# mixer.net
KiCad netlist of a schematic drawn in Altium Designer
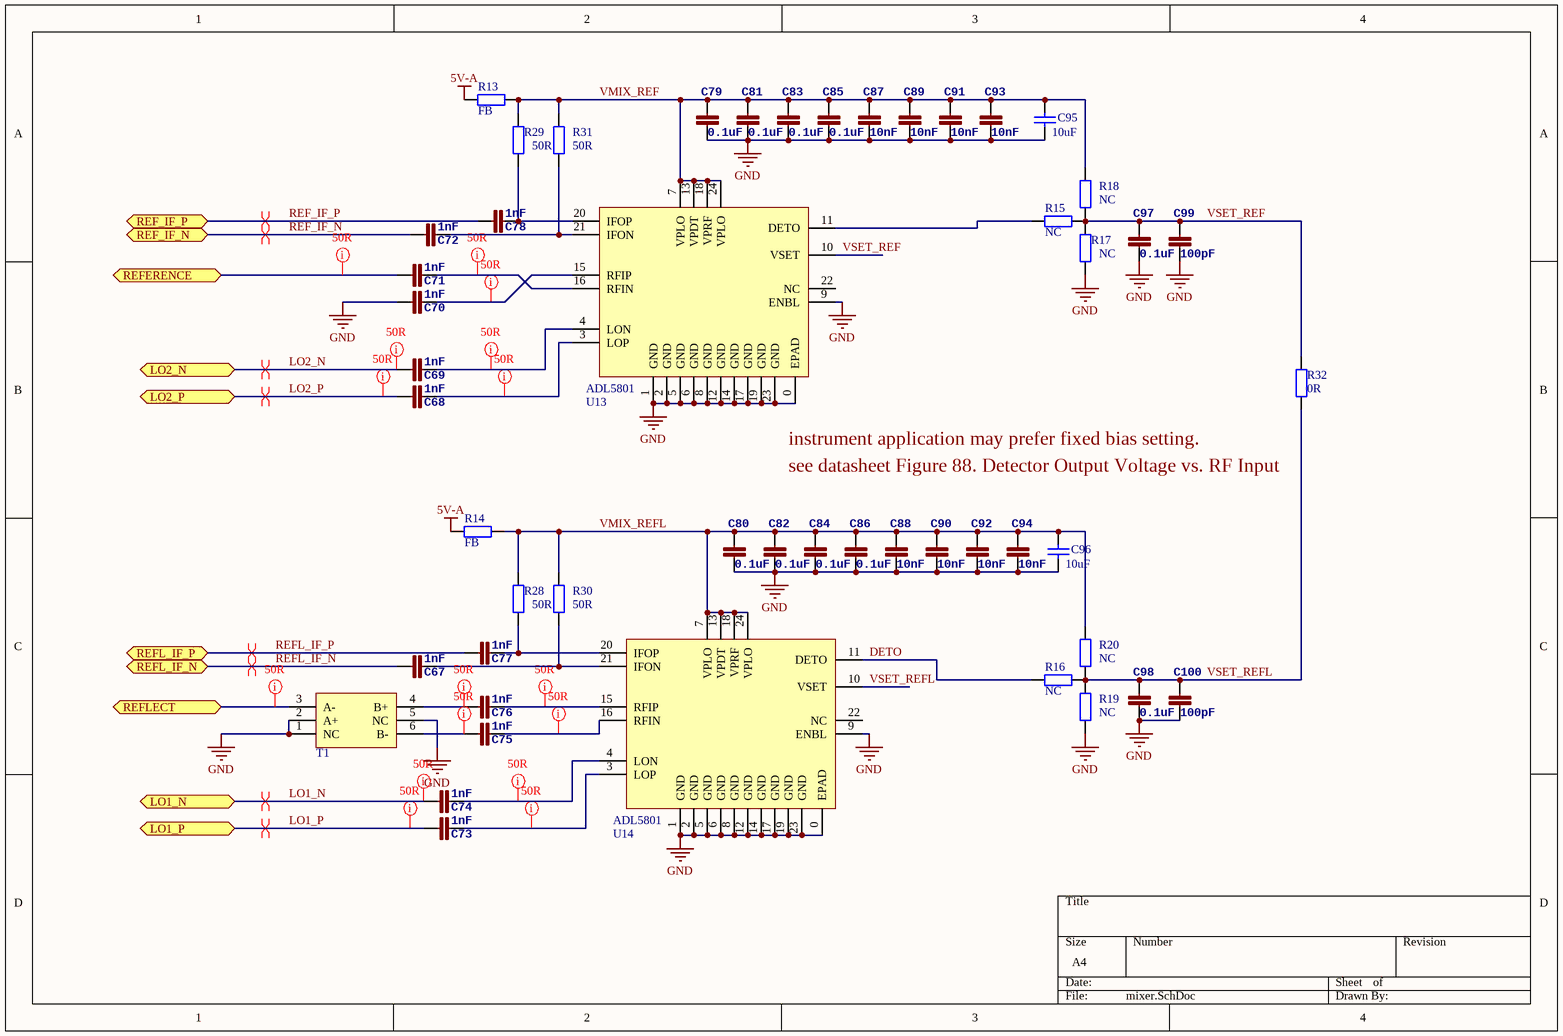
[diagram p0: mixer.SchDoc]

(export (version "E")
  (design (tool "Eeschema 10.0.6"))
  (components
    (comp (ref "C67")
      (value "1nF")
      (footprint "0402")
      (description "<b>Capacitor</b>\nStandard 0603 ceramic capacitor, and 0.1\" leaded capacitor.")
      (fields (field (name "PARTNO") "CC0402ZRY5V7BB104"))
      (libsource (lib "*") (part "CAP0402-CAP"))
    )
    (comp (ref "C68")
      (value "1nF")
      (footprint "0402")
      (description "<b>Capacitor</b>\nStandard 0603 ceramic capacitor, and 0.1\" leaded capacitor.")
      (fields (field (name "PARTNO") "CC0402ZRY5V7BB104"))
      (libsource (lib "*") (part "CAP0402-CAP"))
    )
    (comp (ref "C69")
      (value "1nF")
      (footprint "0402")
      (description "<b>Capacitor</b>\nStandard 0603 ceramic capacitor, and 0.1\" leaded capacitor.")
      (fields (field (name "PARTNO") "CC0402ZRY5V7BB104"))
      (libsource (lib "*") (part "CAP0402-CAP"))
    )
    (comp (ref "C70")
      (value "1nF")
      (footprint "0402")
      (description "<b>Capacitor</b>\nStandard 0603 ceramic capacitor, and 0.1\" leaded capacitor.")
      (fields (field (name "PARTNO") "CC0402ZRY5V7BB104"))
      (libsource (lib "*") (part "CAP0402-CAP"))
    )
    (comp (ref "C71")
      (value "1nF")
      (footprint "0402")
      (description "<b>Capacitor</b>\nStandard 0603 ceramic capacitor, and 0.1\" leaded capacitor.")
      (fields (field (name "PARTNO") "CC0402ZRY5V7BB104"))
      (libsource (lib "*") (part "CAP0402-CAP"))
    )
    (comp (ref "C72")
      (value "1nF")
      (footprint "0402")
      (description "<b>Capacitor</b>\nStandard 0603 ceramic capacitor, and 0.1\" leaded capacitor.")
      (fields (field (name "PARTNO") "CC0402ZRY5V7BB104"))
      (libsource (lib "*") (part "CAP0402-CAP"))
    )
    (comp (ref "C73")
      (value "1nF")
      (footprint "0402")
      (description "<b>Capacitor</b>\nStandard 0603 ceramic capacitor, and 0.1\" leaded capacitor.")
      (fields (field (name "PARTNO") "CC0402ZRY5V7BB104"))
      (libsource (lib "*") (part "CAP0402-CAP"))
    )
    (comp (ref "C74")
      (value "1nF")
      (footprint "0402")
      (description "<b>Capacitor</b>\nStandard 0603 ceramic capacitor, and 0.1\" leaded capacitor.")
      (fields (field (name "PARTNO") "CC0402ZRY5V7BB104"))
      (libsource (lib "*") (part "CAP0402-CAP"))
    )
    (comp (ref "C75")
      (value "1nF")
      (footprint "0402")
      (description "<b>Capacitor</b>\nStandard 0603 ceramic capacitor, and 0.1\" leaded capacitor.")
      (fields (field (name "PARTNO") "CC0402ZRY5V7BB104"))
      (libsource (lib "*") (part "CAP0402-CAP"))
    )
    (comp (ref "C76")
      (value "1nF")
      (footprint "0402")
      (description "<b>Capacitor</b>\nStandard 0603 ceramic capacitor, and 0.1\" leaded capacitor.")
      (fields (field (name "PARTNO") "CC0402ZRY5V7BB104"))
      (libsource (lib "*") (part "CAP0402-CAP"))
    )
    (comp (ref "C77")
      (value "1nF")
      (footprint "0402")
      (description "<b>Capacitor</b>\nStandard 0603 ceramic capacitor, and 0.1\" leaded capacitor.")
      (fields (field (name "PARTNO") "CC0402ZRY5V7BB104"))
      (libsource (lib "*") (part "CAP0402-CAP"))
    )
    (comp (ref "C78")
      (value "1nF")
      (footprint "0402")
      (description "<b>Capacitor</b>\nStandard 0603 ceramic capacitor, and 0.1\" leaded capacitor.")
      (fields (field (name "PARTNO") "CC0402ZRY5V7BB104"))
      (libsource (lib "*") (part "CAP0402-CAP"))
    )
    (comp (ref "C79")
      (value "0.1uF")
      (footprint "0402")
      (description "<b>Capacitor</b>\nStandard 0603 ceramic capacitor, and 0.1\" leaded capacitor.")
      (fields (field (name "PARTNO") "CC0402ZRY5V7BB104"))
      (libsource (lib "") (part "CAP0402-CAP_1"))
    )
    (comp (ref "C80")
      (value "0.1uF")
      (footprint "0402")
      (description "<b>Capacitor</b>\nStandard 0603 ceramic capacitor, and 0.1\" leaded capacitor.")
      (fields (field (name "PARTNO") "CC0402ZRY5V7BB104"))
      (libsource (lib "") (part "CAP0402-CAP_1"))
    )
    (comp (ref "C81")
      (value "0.1uF")
      (footprint "0402")
      (description "<b>Capacitor</b>\nStandard 0603 ceramic capacitor, and 0.1\" leaded capacitor.")
      (fields (field (name "PARTNO") "CC0402ZRY5V7BB104"))
      (libsource (lib "") (part "CAP0402-CAP_1"))
    )
    (comp (ref "C82")
      (value "0.1uF")
      (footprint "0402")
      (description "<b>Capacitor</b>\nStandard 0603 ceramic capacitor, and 0.1\" leaded capacitor.")
      (fields (field (name "PARTNO") "CC0402ZRY5V7BB104"))
      (libsource (lib "") (part "CAP0402-CAP_1"))
    )
    (comp (ref "C83")
      (value "0.1uF")
      (footprint "0402")
      (description "<b>Capacitor</b>\nStandard 0603 ceramic capacitor, and 0.1\" leaded capacitor.")
      (fields (field (name "PARTNO") "CC0402ZRY5V7BB104"))
      (libsource (lib "") (part "CAP0402-CAP_1"))
    )
    (comp (ref "C84")
      (value "0.1uF")
      (footprint "0402")
      (description "<b>Capacitor</b>\nStandard 0603 ceramic capacitor, and 0.1\" leaded capacitor.")
      (fields (field (name "PARTNO") "CC0402ZRY5V7BB104"))
      (libsource (lib "") (part "CAP0402-CAP_1"))
    )
    (comp (ref "C85")
      (value "0.1uF")
      (footprint "0402")
      (description "<b>Capacitor</b>\nStandard 0603 ceramic capacitor, and 0.1\" leaded capacitor.")
      (fields (field (name "PARTNO") "CC0402ZRY5V7BB104"))
      (libsource (lib "") (part "CAP0402-CAP_1"))
    )
    (comp (ref "C86")
      (value "0.1uF")
      (footprint "0402")
      (description "<b>Capacitor</b>\nStandard 0603 ceramic capacitor, and 0.1\" leaded capacitor.")
      (fields (field (name "PARTNO") "CC0402ZRY5V7BB104"))
      (libsource (lib "") (part "CAP0402-CAP_1"))
    )
    (comp (ref "C87")
      (value "10nF")
      (footprint "0402")
      (description "<b>Capacitor</b>\nStandard 0603 ceramic capacitor, and 0.1\" leaded capacitor.")
      (fields (field (name "PARTNO") "CC0402ZRY5V7BB104"))
      (libsource (lib "") (part "CAP0402-CAP_1"))
    )
    (comp (ref "C88")
      (value "10nF")
      (footprint "0402")
      (description "<b>Capacitor</b>\nStandard 0603 ceramic capacitor, and 0.1\" leaded capacitor.")
      (fields (field (name "PARTNO") "CC0402ZRY5V7BB104"))
      (libsource (lib "") (part "CAP0402-CAP_1"))
    )
    (comp (ref "C89")
      (value "10nF")
      (footprint "0402")
      (description "<b>Capacitor</b>\nStandard 0603 ceramic capacitor, and 0.1\" leaded capacitor.")
      (fields (field (name "PARTNO") "CC0402ZRY5V7BB104"))
      (libsource (lib "") (part "CAP0402-CAP_1"))
    )
    (comp (ref "C90")
      (value "10nF")
      (footprint "0402")
      (description "<b>Capacitor</b>\nStandard 0603 ceramic capacitor, and 0.1\" leaded capacitor.")
      (fields (field (name "PARTNO") "CC0402ZRY5V7BB104"))
      (libsource (lib "") (part "CAP0402-CAP_1"))
    )
    (comp (ref "C91")
      (value "10nF")
      (footprint "0402")
      (description "<b>Capacitor</b>\nStandard 0603 ceramic capacitor, and 0.1\" leaded capacitor.")
      (fields (field (name "PARTNO") "CC0402ZRY5V7BB104"))
      (libsource (lib "") (part "CAP0402-CAP_1"))
    )
    (comp (ref "C92")
      (value "10nF")
      (footprint "0402")
      (description "<b>Capacitor</b>\nStandard 0603 ceramic capacitor, and 0.1\" leaded capacitor.")
      (fields (field (name "PARTNO") "CC0402ZRY5V7BB104"))
      (libsource (lib "") (part "CAP0402-CAP_1"))
    )
    (comp (ref "C93")
      (value "10nF")
      (footprint "0402")
      (description "<b>Capacitor</b>\nStandard 0603 ceramic capacitor, and 0.1\" leaded capacitor.")
      (fields (field (name "PARTNO") "CC0402ZRY5V7BB104"))
      (libsource (lib "") (part "CAP0402-CAP_1"))
    )
    (comp (ref "C94")
      (value "10nF")
      (footprint "0402")
      (description "<b>Capacitor</b>\nStandard 0603 ceramic capacitor, and 0.1\" leaded capacitor.")
      (fields (field (name "PARTNO") "CC0402ZRY5V7BB104"))
      (libsource (lib "") (part "CAP0402-CAP_1"))
    )
    (comp (ref "C95")
      (value "10uF")
      (footprint "0805")
      (description "Capacitor")
      (fields (field (name "PUBLISHER") "Altium Limited"))
      (libsource (lib "RTC6705") (part "Cap"))
    )
    (comp (ref "C96")
      (value "10uF")
      (footprint "0805")
      (description "Capacitor")
      (fields (field (name "PUBLISHER") "Altium Limited"))
      (libsource (lib "RTC6705") (part "Cap"))
    )
    (comp (ref "C97")
      (value "0.1uF")
      (footprint "0402")
      (description "<b>Capacitor</b>\nStandard 0603 ceramic capacitor, and 0.1\" leaded capacitor.")
      (fields (field (name "PARTNO") "CC0402ZRY5V7BB104"))
      (libsource (lib "") (part "CAP0402-CAP_1"))
    )
    (comp (ref "C98")
      (value "0.1uF")
      (footprint "0402")
      (description "<b>Capacitor</b>\nStandard 0603 ceramic capacitor, and 0.1\" leaded capacitor.")
      (fields (field (name "PARTNO") "CC0402ZRY5V7BB104"))
      (libsource (lib "") (part "CAP0402-CAP_1"))
    )
    (comp (ref "C99")
      (value "100pF")
      (footprint "0402")
      (description "<b>Capacitor</b>\nStandard 0603 ceramic capacitor, and 0.1\" leaded capacitor.")
      (fields (field (name "PARTNO") "CC0402ZRY5V7BB104"))
      (libsource (lib "") (part "CAP0402-CAP_1"))
    )
    (comp (ref "C100")
      (value "100pF")
      (footprint "0402")
      (description "<b>Capacitor</b>\nStandard 0603 ceramic capacitor, and 0.1\" leaded capacitor.")
      (fields (field (name "PARTNO") "CC0402ZRY5V7BB104"))
      (libsource (lib "") (part "CAP0402-CAP_1"))
    )
    (comp (ref "R13")
      (value "FB")
      (footprint "0603")
      (description "Resistor")
      (fields (field (name "PUBLISHER") "Altium Limited"))
      (libsource (lib "Miscellaneous Devices") (part "Res2"))
    )
    (comp (ref "R14")
      (value "FB")
      (footprint "0603")
      (description "Resistor")
      (fields (field (name "PUBLISHER") "Altium Limited"))
      (libsource (lib "Miscellaneous Devices") (part "Res2"))
    )
    (comp (ref "R15")
      (value "NC")
      (footprint "0402")
      (description "Resistor")
      (fields (field (name "PUBLISHER") "Altium Limited"))
      (libsource (lib "") (part "Res2_2"))
    )
    (comp (ref "R16")
      (value "NC")
      (footprint "0402")
      (description "Resistor")
      (fields (field (name "PUBLISHER") "Altium Limited"))
      (libsource (lib "") (part "Res2_2"))
    )
    (comp (ref "R17")
      (value "NC")
      (footprint "0402")
      (description "Resistor")
      (fields (field (name "PUBLISHER") "Altium Limited"))
      (libsource (lib "RTC6705") (part "Res2"))
    )
    (comp (ref "R18")
      (value "NC")
      (footprint "0402")
      (description "Resistor")
      (fields (field (name "PUBLISHER") "Altium Limited"))
      (libsource (lib "RTC6705") (part "Res2"))
    )
    (comp (ref "R19")
      (value "NC")
      (footprint "0402")
      (description "Resistor")
      (fields (field (name "PUBLISHER") "Altium Limited"))
      (libsource (lib "RTC6705") (part "Res2"))
    )
    (comp (ref "R20")
      (value "NC")
      (footprint "0402")
      (description "Resistor")
      (fields (field (name "PUBLISHER") "Altium Limited"))
      (libsource (lib "RTC6705") (part "Res2"))
    )
    (comp (ref "R28")
      (value "50R")
      (footprint "0402")
      (description "Resistor")
      (fields (field (name "PUBLISHER") "Altium Limited"))
      (libsource (lib "RTC6705") (part "Res2"))
    )
    (comp (ref "R29")
      (value "50R")
      (footprint "0402")
      (description "Resistor")
      (fields (field (name "PUBLISHER") "Altium Limited"))
      (libsource (lib "RTC6705") (part "Res2"))
    )
    (comp (ref "R30")
      (value "50R")
      (footprint "0402")
      (description "Resistor")
      (fields (field (name "PUBLISHER") "Altium Limited"))
      (libsource (lib "RTC6705") (part "Res2"))
    )
    (comp (ref "R31")
      (value "50R")
      (footprint "0402")
      (description "Resistor")
      (fields (field (name "PUBLISHER") "Altium Limited"))
      (libsource (lib "RTC6705") (part "Res2"))
    )
    (comp (ref "R32")
      (value "0R")
      (footprint "0402")
      (description "Resistor")
      (fields (field (name "PUBLISHER") "Altium Limited"))
      (libsource (lib "") (part "Res2_1"))
    )
    (comp (ref "T1")
      (value "TCM1-63AX+")
      (footprint "TCM1-63AX+")
      (libsource (lib "F4SDR") (part "TCM1-63AX+"))
    )
    (comp (ref "U13") (value "ADL5801") (footprint "ADL5801") (libsource (lib "F4SDR") (part "ADL5801")))
    (comp (ref "U14") (value "ADL5801") (footprint "ADL5801") (libsource (lib "F4SDR") (part "ADL5801")))
  )
  (nets
    (net (code "1") (name "/DETO") (class "Default")
      (node (ref "R16") (pin "2") (pinfunction "2_2") (pintype "passive"))
      (node (ref "U14") (pin "11") (pinfunction "DETO_11") (pintype "passive"))
    )
    (net (code "2") (name "/LO1_N") (class "Default")
      (node (ref "C74") (pin "1") (pinfunction "1_1") (pintype "passive"))
    )
    (net (code "3") (name "/LO1_P") (class "Default")
      (node (ref "C73") (pin "1") (pinfunction "1_1") (pintype "passive"))
    )
    (net (code "4") (name "/LO2_N") (class "Default")
      (node (ref "C69") (pin "1") (pinfunction "1_1") (pintype "passive"))
    )
    (net (code "5") (name "/LO2_P") (class "Default")
      (node (ref "C68") (pin "1") (pinfunction "1_1") (pintype "passive"))
    )
    (net (code "6") (name "/REFERENCE") (class "Default")
      (node (ref "C71") (pin "1") (pinfunction "1_1") (pintype "passive"))
    )
    (net (code "7") (name "/REFLECT") (class "Default")
      (node (ref "T1") (pin "3") (pinfunction "A-_3") (pintype "passive"))
    )
    (net (code "8") (name "/REFL_IF_N") (class "Default")
      (node (ref "C67") (pin "1") (pinfunction "1_1") (pintype "passive"))
    )
    (net (code "9") (name "/REFL_IF_P") (class "Default")
      (node (ref "C77") (pin "1") (pinfunction "1_1") (pintype "passive"))
    )
    (net (code "10") (name "/REF_IF_N") (class "Default")
      (node (ref "C72") (pin "1") (pinfunction "1_1") (pintype "passive"))
    )
    (net (code "11") (name "/REF_IF_P") (class "Default")
      (node (ref "C78") (pin "1") (pinfunction "1_1") (pintype "passive"))
    )
    (net (code "12") (name "/VMIX_REF") (class "Default")
      (node (ref "C79") (pin "2") (pinfunction "2_2") (pintype "passive"))
      (node (ref "C81") (pin "2") (pinfunction "2_2") (pintype "passive"))
      (node (ref "C83") (pin "2") (pinfunction "2_2") (pintype "passive"))
      (node (ref "C85") (pin "2") (pinfunction "2_2") (pintype "passive"))
      (node (ref "C87") (pin "2") (pinfunction "2_2") (pintype "passive"))
      (node (ref "C89") (pin "2") (pinfunction "2_2") (pintype "passive"))
      (node (ref "C91") (pin "2") (pinfunction "2_2") (pintype "passive"))
      (node (ref "C93") (pin "2") (pinfunction "2_2") (pintype "passive"))
      (node (ref "C95") (pin "2") (pinfunction "2_2") (pintype "passive"))
      (node (ref "R13") (pin "2") (pinfunction "2_2") (pintype "passive"))
      (node (ref "R18") (pin "2") (pinfunction "2_2") (pintype "passive"))
      (node (ref "R29") (pin "2") (pinfunction "2_2") (pintype "passive"))
      (node (ref "R31") (pin "2") (pinfunction "2_2") (pintype "passive"))
      (node (ref "U13") (pin "13") (pinfunction "VPDT_13") (pintype "passive"))
      (node (ref "U13") (pin "18") (pinfunction "VPRF_18") (pintype "passive"))
      (node (ref "U13") (pin "24") (pinfunction "VPLO_24") (pintype "passive"))
      (node (ref "U13") (pin "7") (pinfunction "VPLO_7") (pintype "passive"))
    )
    (net (code "13") (name "/VMIX_REFL") (class "Default")
      (node (ref "C80") (pin "2") (pinfunction "2_2") (pintype "passive"))
      (node (ref "C82") (pin "2") (pinfunction "2_2") (pintype "passive"))
      (node (ref "C84") (pin "2") (pinfunction "2_2") (pintype "passive"))
      (node (ref "C86") (pin "2") (pinfunction "2_2") (pintype "passive"))
      (node (ref "C88") (pin "2") (pinfunction "2_2") (pintype "passive"))
      (node (ref "C90") (pin "2") (pinfunction "2_2") (pintype "passive"))
      (node (ref "C92") (pin "2") (pinfunction "2_2") (pintype "passive"))
      (node (ref "C94") (pin "2") (pinfunction "2_2") (pintype "passive"))
      (node (ref "C96") (pin "2") (pinfunction "2_2") (pintype "passive"))
      (node (ref "R14") (pin "2") (pinfunction "2_2") (pintype "passive"))
      (node (ref "R20") (pin "2") (pinfunction "2_2") (pintype "passive"))
      (node (ref "R28") (pin "2") (pinfunction "2_2") (pintype "passive"))
      (node (ref "R30") (pin "2") (pinfunction "2_2") (pintype "passive"))
      (node (ref "U14") (pin "13") (pinfunction "VPDT_13") (pintype "passive"))
      (node (ref "U14") (pin "18") (pinfunction "VPRF_18") (pintype "passive"))
      (node (ref "U14") (pin "24") (pinfunction "VPLO_24") (pintype "passive"))
      (node (ref "U14") (pin "7") (pinfunction "VPLO_7") (pintype "passive"))
    )
    (net (code "14") (name "/VSET_REF") (class "Default")
      (node (ref "C97") (pin "2") (pinfunction "2_2") (pintype "passive"))
      (node (ref "C99") (pin "2") (pinfunction "2_2") (pintype "passive"))
      (node (ref "R15") (pin "1") (pinfunction "1_1") (pintype "passive"))
      (node (ref "R17") (pin "2") (pinfunction "2_2") (pintype "passive"))
      (node (ref "R18") (pin "1") (pinfunction "1_1") (pintype "passive"))
      (node (ref "R32") (pin "1") (pinfunction "1_1") (pintype "passive"))
      (node (ref "U13") (pin "10") (pinfunction "VSET_10") (pintype "passive"))
    )
    (net (code "15") (name "/VSET_REFL") (class "Default")
      (node (ref "C100") (pin "2") (pinfunction "2_2") (pintype "passive"))
      (node (ref "C98") (pin "2") (pinfunction "2_2") (pintype "passive"))
      (node (ref "R16") (pin "1") (pinfunction "1_1") (pintype "passive"))
      (node (ref "R19") (pin "2") (pinfunction "2_2") (pintype "passive"))
      (node (ref "R20") (pin "1") (pinfunction "1_1") (pintype "passive"))
      (node (ref "R32") (pin "2") (pinfunction "2_2") (pintype "passive"))
      (node (ref "U14") (pin "10") (pinfunction "VSET_10") (pintype "passive"))
    )
    (net (code "16") (name "5V-A") (class "Default")
      (node (ref "R13") (pin "1") (pinfunction "1_1") (pintype "passive"))
      (node (ref "R14") (pin "1") (pinfunction "1_1") (pintype "passive"))
    )
    (net (code "17") (name "GND") (class "Default")
      (node (ref "C100") (pin "1") (pinfunction "1_1") (pintype "passive"))
      (node (ref "C70") (pin "1") (pinfunction "1_1") (pintype "passive"))
      (node (ref "C79") (pin "1") (pinfunction "1_1") (pintype "passive"))
      (node (ref "C80") (pin "1") (pinfunction "1_1") (pintype "passive"))
      (node (ref "C81") (pin "1") (pinfunction "1_1") (pintype "passive"))
      (node (ref "C82") (pin "1") (pinfunction "1_1") (pintype "passive"))
      (node (ref "C83") (pin "1") (pinfunction "1_1") (pintype "passive"))
      (node (ref "C84") (pin "1") (pinfunction "1_1") (pintype "passive"))
      (node (ref "C85") (pin "1") (pinfunction "1_1") (pintype "passive"))
      (node (ref "C86") (pin "1") (pinfunction "1_1") (pintype "passive"))
      (node (ref "C87") (pin "1") (pinfunction "1_1") (pintype "passive"))
      (node (ref "C88") (pin "1") (pinfunction "1_1") (pintype "passive"))
      (node (ref "C89") (pin "1") (pinfunction "1_1") (pintype "passive"))
      (node (ref "C90") (pin "1") (pinfunction "1_1") (pintype "passive"))
      (node (ref "C91") (pin "1") (pinfunction "1_1") (pintype "passive"))
      (node (ref "C92") (pin "1") (pinfunction "1_1") (pintype "passive"))
      (node (ref "C93") (pin "1") (pinfunction "1_1") (pintype "passive"))
      (node (ref "C94") (pin "1") (pinfunction "1_1") (pintype "passive"))
      (node (ref "C95") (pin "1") (pinfunction "1_1") (pintype "passive"))
      (node (ref "C96") (pin "1") (pinfunction "1_1") (pintype "passive"))
      (node (ref "C97") (pin "1") (pinfunction "1_1") (pintype "passive"))
      (node (ref "C98") (pin "1") (pinfunction "1_1") (pintype "passive"))
      (node (ref "C99") (pin "1") (pinfunction "1_1") (pintype "passive"))
      (node (ref "R17") (pin "1") (pinfunction "1_1") (pintype "passive"))
      (node (ref "R19") (pin "1") (pinfunction "1_1") (pintype "passive"))
      (node (ref "T1") (pin "1") (pinfunction "NC_1") (pintype "passive"))
      (node (ref "T1") (pin "2") (pinfunction "A+_2") (pintype "passive"))
      (node (ref "T1") (pin "5") (pinfunction "NC_5") (pintype "passive"))
      (node (ref "U13") (pin "0") (pinfunction "EPAD_0") (pintype "passive"))
      (node (ref "U13") (pin "1") (pinfunction "GND_1") (pintype "passive"))
      (node (ref "U13") (pin "12") (pinfunction "GND_12") (pintype "passive"))
      (node (ref "U13") (pin "14") (pinfunction "GND_14") (pintype "passive"))
      (node (ref "U13") (pin "17") (pinfunction "GND_17") (pintype "passive"))
      (node (ref "U13") (pin "19") (pinfunction "GND_19") (pintype "passive"))
      (node (ref "U13") (pin "2") (pinfunction "GND_2") (pintype "passive"))
      (node (ref "U13") (pin "23") (pinfunction "GND_23") (pintype "passive"))
      (node (ref "U13") (pin "5") (pinfunction "GND_5") (pintype "passive"))
      (node (ref "U13") (pin "6") (pinfunction "GND_6") (pintype "passive"))
      (node (ref "U13") (pin "8") (pinfunction "GND_8") (pintype "passive"))
      (node (ref "U13") (pin "9") (pinfunction "ENBL_9") (pintype "passive"))
      (node (ref "U14") (pin "0") (pinfunction "EPAD_0") (pintype "passive"))
      (node (ref "U14") (pin "1") (pinfunction "GND_1") (pintype "passive"))
      (node (ref "U14") (pin "12") (pinfunction "GND_12") (pintype "passive"))
      (node (ref "U14") (pin "14") (pinfunction "GND_14") (pintype "passive"))
      (node (ref "U14") (pin "17") (pinfunction "GND_17") (pintype "passive"))
      (node (ref "U14") (pin "19") (pinfunction "GND_19") (pintype "passive"))
      (node (ref "U14") (pin "2") (pinfunction "GND_2") (pintype "passive"))
      (node (ref "U14") (pin "23") (pinfunction "GND_23") (pintype "passive"))
      (node (ref "U14") (pin "5") (pinfunction "GND_5") (pintype "passive"))
      (node (ref "U14") (pin "6") (pinfunction "GND_6") (pintype "passive"))
      (node (ref "U14") (pin "8") (pinfunction "GND_8") (pintype "passive"))
      (node (ref "U14") (pin "9") (pinfunction "ENBL_9") (pintype "passive"))
    )
    (net (code "18") (name "Net-(T1-B+)") (class "Default")
      (node (ref "C76") (pin "1") (pinfunction "1_1") (pintype "passive"))
      (node (ref "T1") (pin "4") (pinfunction "B+_4") (pintype "passive"))
    )
    (net (code "19") (name "Net-(T1-B-)") (class "Default")
      (node (ref "C75") (pin "1") (pinfunction "1_1") (pintype "passive"))
      (node (ref "T1") (pin "6") (pinfunction "B-_6") (pintype "passive"))
    )
    (net (code "20") (name "Net-(U13-DETO)") (class "Default")
      (node (ref "R15") (pin "2") (pinfunction "2_2") (pintype "passive"))
      (node (ref "U13") (pin "11") (pinfunction "DETO_11") (pintype "passive"))
    )
    (net (code "21") (name "Net-(U13-IFON)") (class "Default")
      (node (ref "C72") (pin "2") (pinfunction "2_2") (pintype "passive"))
      (node (ref "R31") (pin "1") (pinfunction "1_1") (pintype "passive"))
      (node (ref "U13") (pin "21") (pinfunction "IFON_21") (pintype "passive"))
    )
    (net (code "22") (name "Net-(U13-IFOP)") (class "Default")
      (node (ref "C78") (pin "2") (pinfunction "2_2") (pintype "passive"))
      (node (ref "R29") (pin "1") (pinfunction "1_1") (pintype "passive"))
      (node (ref "U13") (pin "20") (pinfunction "IFOP_20") (pintype "passive"))
    )
    (net (code "23") (name "Net-(U13-LON)") (class "Default")
      (node (ref "C69") (pin "2") (pinfunction "2_2") (pintype "passive"))
      (node (ref "U13") (pin "4") (pinfunction "LON_4") (pintype "passive"))
    )
    (net (code "24") (name "Net-(U13-LOP)") (class "Default")
      (node (ref "C68") (pin "2") (pinfunction "2_2") (pintype "passive"))
      (node (ref "U13") (pin "3") (pinfunction "LOP_3") (pintype "passive"))
    )
    (net (code "25") (name "Net-(U13-RFIN)") (class "Default")
      (node (ref "C71") (pin "2") (pinfunction "2_2") (pintype "passive"))
      (node (ref "U13") (pin "16") (pinfunction "RFIN_16") (pintype "passive"))
    )
    (net (code "26") (name "Net-(U13-RFIP)") (class "Default")
      (node (ref "C70") (pin "2") (pinfunction "2_2") (pintype "passive"))
      (node (ref "U13") (pin "15") (pinfunction "RFIP_15") (pintype "passive"))
    )
    (net (code "27") (name "Net-(U14-IFON)") (class "Default")
      (node (ref "C67") (pin "2") (pinfunction "2_2") (pintype "passive"))
      (node (ref "R30") (pin "1") (pinfunction "1_1") (pintype "passive"))
      (node (ref "U14") (pin "21") (pinfunction "IFON_21") (pintype "passive"))
    )
    (net (code "28") (name "Net-(U14-IFOP)") (class "Default")
      (node (ref "C77") (pin "2") (pinfunction "2_2") (pintype "passive"))
      (node (ref "R28") (pin "1") (pinfunction "1_1") (pintype "passive"))
      (node (ref "U14") (pin "20") (pinfunction "IFOP_20") (pintype "passive"))
    )
    (net (code "29") (name "Net-(U14-LON)") (class "Default")
      (node (ref "C74") (pin "2") (pinfunction "2_2") (pintype "passive"))
      (node (ref "U14") (pin "4") (pinfunction "LON_4") (pintype "passive"))
    )
    (net (code "30") (name "Net-(U14-LOP)") (class "Default")
      (node (ref "C73") (pin "2") (pinfunction "2_2") (pintype "passive"))
      (node (ref "U14") (pin "3") (pinfunction "LOP_3") (pintype "passive"))
    )
    (net (code "31") (name "Net-(U14-RFIN)") (class "Default")
      (node (ref "C75") (pin "2") (pinfunction "2_2") (pintype "passive"))
      (node (ref "U14") (pin "16") (pinfunction "RFIN_16") (pintype "passive"))
    )
    (net (code "32") (name "Net-(U14-RFIP)") (class "Default")
      (node (ref "C76") (pin "2") (pinfunction "2_2") (pintype "passive"))
      (node (ref "U14") (pin "15") (pinfunction "RFIP_15") (pintype "passive"))
    )
    (net (code "33") (name "unconnected-(U13-NC-Pad22)") (class "Default")
      (node (ref "U13") (pin "22") (pinfunction "NC_22") (pintype "passive"))
    )
    (net (code "34") (name "unconnected-(U14-NC-Pad22)") (class "Default")
      (node (ref "U14") (pin "22") (pinfunction "NC_22") (pintype "passive"))
    )
  )
)
